# McPiFace-V1.net
KiCad netlist of a schematic drawn in EAGLE
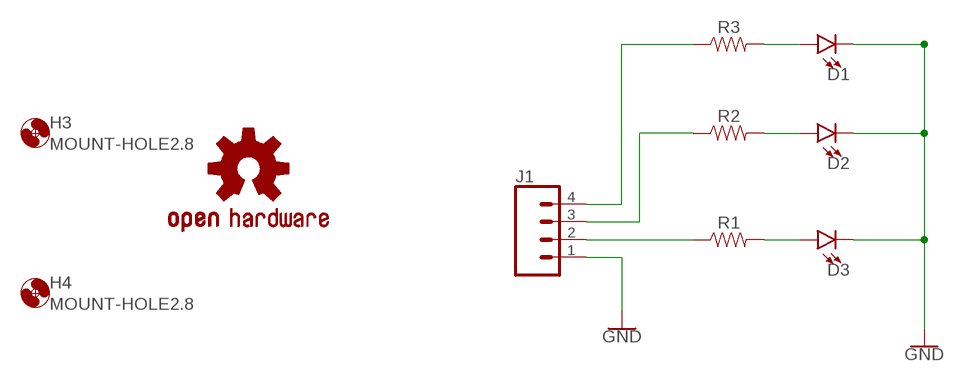
[diagram p0: schematic, sheet 1]

(export (version "E")
  (design (tool "Eeschema 10.0.6"))
  (components
    (comp (ref "D1")
      (value "LED1206-BOTTOM-1.6MM")
      (footprint "eagle-import:LED-1206-BOTTOM-1.6MM")
      (libsource (lib "eagle-import") (part "LED1206-BOTTOM-1.6MM"))
    )
    (comp (ref "D2")
      (value "LED1206-BOTTOM-1.6MM")
      (footprint "eagle-import:LED-1206-BOTTOM-1.6MM")
      (libsource (lib "eagle-import") (part "LED1206-BOTTOM-1.6MM"))
    )
    (comp (ref "D3")
      (value "LED1206-BOTTOM-1.6MM")
      (footprint "eagle-import:LED-1206-BOTTOM-1.6MM")
      (libsource (lib "eagle-import") (part "LED1206-BOTTOM-1.6MM"))
    )
    (comp (ref "H3")
      (value "MOUNT-HOLE2.8")
      (footprint "eagle-import:2,8")
      (libsource (lib "eagle-import") (part "MOUNT-HOLE2.8"))
    )
    (comp (ref "H4")
      (value "MOUNT-HOLE2.8")
      (footprint "eagle-import:2,8")
      (libsource (lib "eagle-import") (part "MOUNT-HOLE2.8"))
    )
    (comp (ref "J1")
      (value "CONN_04SMD2")
      (footprint "eagle-import:1X04_1MM_RA")
      (libsource (lib "eagle-import") (part "CONN_04SMD2"))
    )
    (comp (ref "LOGO1")
      (value "OSHW-LOGOL")
      (footprint "eagle-import:OSHW-LOGO-L")
      (libsource (lib "eagle-import") (part "OSHW-LOGOL"))
    )
    (comp (ref "R1")
      (value "RESISTOR1206")
      (footprint "eagle-import:1206")
      (libsource (lib "eagle-import") (part "RESISTOR1206"))
    )
    (comp (ref "R2")
      (value "RESISTOR1206")
      (footprint "eagle-import:1206")
      (libsource (lib "eagle-import") (part "RESISTOR1206"))
    )
    (comp (ref "R3")
      (value "RESISTOR1206")
      (footprint "eagle-import:1206")
      (libsource (lib "eagle-import") (part "RESISTOR1206"))
    )
  )
  (nets
    (net (code "1") (name "GND") (class "Default")
      (node (ref "D1") (pin "C") (pinfunction "C_C") (pintype "passive"))
      (node (ref "D2") (pin "C") (pinfunction "C_C") (pintype "passive"))
      (node (ref "D3") (pin "C") (pinfunction "C_C") (pintype "passive"))
      (node (ref "J1") (pin "1") (pinfunction "1_1") (pintype "passive"))
    )
    (net (code "2") (name "Net-(D1-PadA)") (class "Default")
      (node (ref "D1") (pin "A") (pinfunction "A_A") (pintype "passive"))
      (node (ref "R3") (pin "2") (pinfunction "2_2") (pintype "passive"))
    )
    (net (code "3") (name "Net-(D2-PadA)") (class "Default")
      (node (ref "D2") (pin "A") (pinfunction "A_A") (pintype "passive"))
      (node (ref "R2") (pin "2") (pinfunction "2_2") (pintype "passive"))
    )
    (net (code "4") (name "Net-(D3-PadA)") (class "Default")
      (node (ref "D3") (pin "A") (pinfunction "A_A") (pintype "passive"))
      (node (ref "R1") (pin "2") (pinfunction "2_2") (pintype "passive"))
    )
    (net (code "5") (name "Net-(J1-Pad2)") (class "Default")
      (node (ref "J1") (pin "2") (pinfunction "2_2") (pintype "passive"))
      (node (ref "R1") (pin "1") (pinfunction "1_1") (pintype "passive"))
    )
    (net (code "6") (name "Net-(J1-Pad3)") (class "Default")
      (node (ref "J1") (pin "3") (pinfunction "3_3") (pintype "passive"))
      (node (ref "R2") (pin "1") (pinfunction "1_1") (pintype "passive"))
    )
    (net (code "7") (name "Net-(J1-Pad4)") (class "Default")
      (node (ref "J1") (pin "4") (pinfunction "4_4") (pintype "passive"))
      (node (ref "R3") (pin "1") (pinfunction "1_1") (pintype "passive"))
    )
  )
)
